# Sensors.net
KiCad netlist of a schematic drawn in Altium Designer
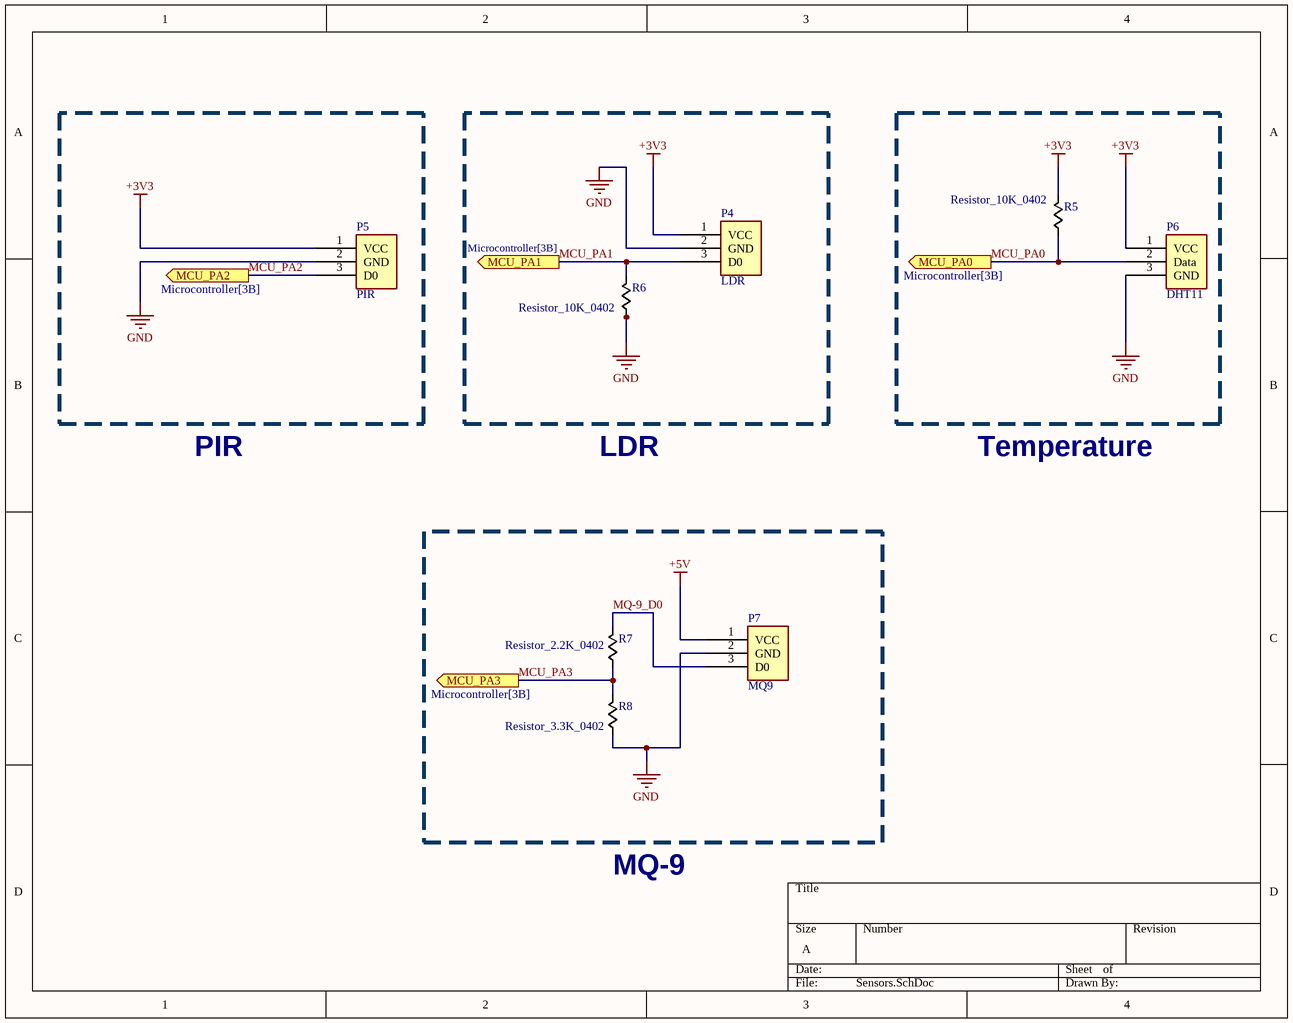
[diagram p0: Sensors.SchDoc]

(export (version "E")
  (design (tool "Eeschema 10.0.6"))
  (components
    (comp (ref "P4")
      (value "LDR")
      (footprint "HEADER 1x3 MALE")
      (libsource (lib "Sensors") (part "Header 1x3-LDR"))
    )
    (comp (ref "P5")
      (value "PIR")
      (footprint "HEADER 1x3 MALE")
      (libsource (lib "Sensors") (part "Header 1x3-PIR"))
    )
    (comp (ref "P6")
      (value "DHT11")
      (footprint "HEADER 1x3 MALE")
      (libsource (lib "Sensors") (part "Header 1x3-DHT Temp"))
    )
    (comp (ref "P7")
      (value "MQ9")
      (footprint "HEADER 1x3 MALE")
      (libsource (lib "Sensors") (part "Header 1x3-MQ9"))
    )
    (comp (ref "R5")
      (value "Resistor_10K_0402")
      (footprint "RESC1005X40N")
      (description "RES 10kΩ ±1% 62.5mW 0402")
      (fields (field (name "MANUFACTURER") "YAGEO") (field (name "MANUFACTURER PART #") "RC0402FR-0710KL"))
      (libsource (lib "Sensors") (part "Resistor_10K_0402"))
    )
    (comp (ref "R6")
      (value "Resistor_10K_0402")
      (footprint "RESC1005X40N")
      (description "RES 10kΩ ±1% 62.5mW 0402")
      (fields (field (name "MANUFACTURER") "YAGEO") (field (name "MANUFACTURER PART #") "RC0402FR-0710KL"))
      (libsource (lib "Sensors") (part "Resistor_10K_0402"))
    )
    (comp (ref "R7")
      (value "Resistor_2.2K_0402")
      (footprint "RESC1005X40N")
      (description "2.2kOhms Â±1% 0.063W, 1/16W Chip Resistor 0402 (1005 Metric) Moisture Resistant Thick Film")
      (fields (field (name "MANUFACTURER") "FOJAN") (field (name "MANUFACTURER PART #") "RC0402FR-071KL"))
      (libsource (lib "Sensors") (part "Resistor_2.2K_0402"))
    )
    (comp (ref "R8")
      (value "Resistor_3.3K_0402")
      (footprint "RESC1005X40N")
      (description "RES 3.3kΩ ±1% 62.5mW 0402")
      (fields (field (name "MANUFACTURER") "YAGEO") (field (name "MANUFACTURER PART #") "RC0402FR-074K7L"))
      (libsource (lib "Sensors") (part "Resistor_3.3K_0402"))
    )
  )
  (nets
    (net (code "1") (name "+3V3") (class "Default")
      (node (ref "P4") (pin "1") (pinfunction "VCC_1") (pintype "passive"))
      (node (ref "P5") (pin "1") (pinfunction "VCC_1") (pintype "passive"))
      (node (ref "P6") (pin "1") (pinfunction "VCC_1") (pintype "passive"))
      (node (ref "R5") (pin "2") (pinfunction "2_2") (pintype "passive"))
    )
    (net (code "2") (name "+5V") (class "Default")
      (node (ref "P7") (pin "1") (pinfunction "VCC_1") (pintype "passive"))
    )
    (net (code "3") (name "/MCU_PA0") (class "Default")
      (node (ref "P6") (pin "2") (pinfunction "Data_2") (pintype "passive"))
      (node (ref "R5") (pin "1") (pinfunction "1_1") (pintype "passive"))
    )
    (net (code "4") (name "/MCU_PA1") (class "Default")
      (node (ref "P4") (pin "3") (pinfunction "D0_3") (pintype "passive"))
      (node (ref "R6") (pin "2") (pinfunction "2_2") (pintype "passive"))
    )
    (net (code "5") (name "/MCU_PA2") (class "Default")
      (node (ref "P5") (pin "3") (pinfunction "D0_3") (pintype "passive"))
    )
    (net (code "6") (name "/MCU_PA3") (class "Default")
      (node (ref "R7") (pin "1") (pinfunction "1_1") (pintype "passive"))
      (node (ref "R8") (pin "2") (pinfunction "2_2") (pintype "passive"))
    )
    (net (code "7") (name "/MQ-9_D0") (class "Default")
      (node (ref "P7") (pin "3") (pinfunction "D0_3") (pintype "passive"))
      (node (ref "R7") (pin "2") (pinfunction "2_2") (pintype "passive"))
    )
    (net (code "8") (name "GND") (class "Default")
      (node (ref "P4") (pin "2") (pinfunction "GND_2") (pintype "passive"))
      (node (ref "P5") (pin "2") (pinfunction "GND_2") (pintype "passive"))
      (node (ref "P6") (pin "3") (pinfunction "GND_3") (pintype "passive"))
      (node (ref "P7") (pin "2") (pinfunction "GND_2") (pintype "passive"))
      (node (ref "R6") (pin "1") (pinfunction "1_1") (pintype "passive"))
      (node (ref "R8") (pin "1") (pinfunction "1_1") (pintype "passive"))
    )
  )
)
